# EWElectrode.net
KiCad netlist of a schematic drawn in EAGLE
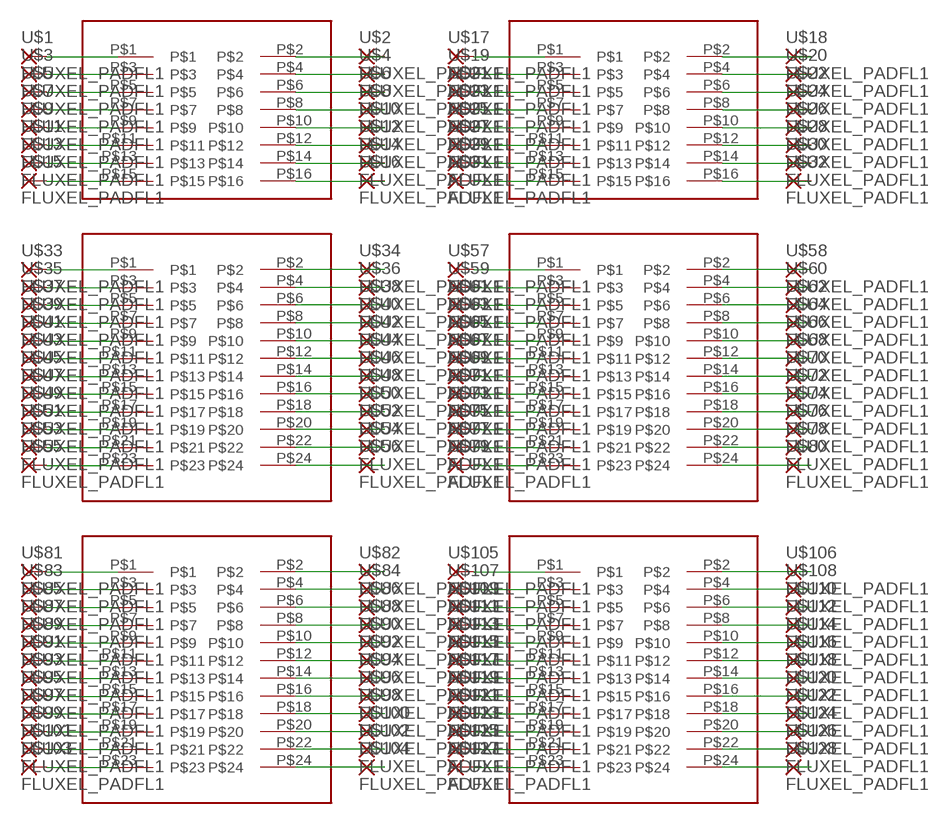
[diagram p0: schematic, sheet 1]

(export (version "E")
  (design (tool "Eeschema 10.0.6"))
  (components
    (comp (ref "J1")
      (value "M20-876P_8X2")
      (footprint "eagle-import:M20-876P_8X2")
      (libsource (lib "eagle-import") (part "M20-876P_8X2"))
    )
    (comp (ref "J2")
      (value "M20-876P_8X2")
      (footprint "eagle-import:M20-876P_8X2")
      (libsource (lib "eagle-import") (part "M20-876P_8X2"))
    )
    (comp (ref "J3")
      (value "M20-876P_12X2")
      (footprint "eagle-import:M20-876P_12X2")
      (libsource (lib "eagle-import") (part "M20-876P_12X2"))
    )
    (comp (ref "J4")
      (value "M20-876P_12X2")
      (footprint "eagle-import:M20-876P_12X2")
      (libsource (lib "eagle-import") (part "M20-876P_12X2"))
    )
    (comp (ref "J5")
      (value "M20-876P_12X2")
      (footprint "eagle-import:M20-876P_12X2")
      (libsource (lib "eagle-import") (part "M20-876P_12X2"))
    )
    (comp (ref "J6")
      (value "M20-876P_12X2")
      (footprint "eagle-import:M20-876P_12X2")
      (libsource (lib "eagle-import") (part "M20-876P_12X2"))
    )
    (comp (ref "U$1")
      (value "FLUXEL_PADFL1")
      (footprint "eagle-import:FLUXEL_PAD")
      (libsource (lib "eagle-import") (part "FLUXEL_PADFL1"))
    )
    (comp (ref "U$2")
      (value "FLUXEL_PADFL1")
      (footprint "eagle-import:FLUXEL_PAD")
      (libsource (lib "eagle-import") (part "FLUXEL_PADFL1"))
    )
    (comp (ref "U$3")
      (value "FLUXEL_PADFL1")
      (footprint "eagle-import:FLUXEL_PAD")
      (libsource (lib "eagle-import") (part "FLUXEL_PADFL1"))
    )
    (comp (ref "U$4")
      (value "FLUXEL_PADFL1")
      (footprint "eagle-import:FLUXEL_PAD")
      (libsource (lib "eagle-import") (part "FLUXEL_PADFL1"))
    )
    (comp (ref "U$5")
      (value "FLUXEL_PADFL1")
      (footprint "eagle-import:FLUXEL_PAD")
      (libsource (lib "eagle-import") (part "FLUXEL_PADFL1"))
    )
    (comp (ref "U$6")
      (value "FLUXEL_PADFL1")
      (footprint "eagle-import:FLUXEL_PAD")
      (libsource (lib "eagle-import") (part "FLUXEL_PADFL1"))
    )
    (comp (ref "U$7")
      (value "FLUXEL_PADFL1")
      (footprint "eagle-import:FLUXEL_PAD")
      (libsource (lib "eagle-import") (part "FLUXEL_PADFL1"))
    )
    (comp (ref "U$8")
      (value "FLUXEL_PADFL1")
      (footprint "eagle-import:FLUXEL_PAD")
      (libsource (lib "eagle-import") (part "FLUXEL_PADFL1"))
    )
    (comp (ref "U$9")
      (value "FLUXEL_PADFL1")
      (footprint "eagle-import:FLUXEL_PAD")
      (libsource (lib "eagle-import") (part "FLUXEL_PADFL1"))
    )
    (comp (ref "U$10")
      (value "FLUXEL_PADFL1")
      (footprint "eagle-import:FLUXEL_PAD")
      (libsource (lib "eagle-import") (part "FLUXEL_PADFL1"))
    )
    (comp (ref "U$11")
      (value "FLUXEL_PADFL1")
      (footprint "eagle-import:FLUXEL_PAD")
      (libsource (lib "eagle-import") (part "FLUXEL_PADFL1"))
    )
    (comp (ref "U$12")
      (value "FLUXEL_PADFL1")
      (footprint "eagle-import:FLUXEL_PAD")
      (libsource (lib "eagle-import") (part "FLUXEL_PADFL1"))
    )
    (comp (ref "U$13")
      (value "FLUXEL_PADFL1")
      (footprint "eagle-import:FLUXEL_PAD")
      (libsource (lib "eagle-import") (part "FLUXEL_PADFL1"))
    )
    (comp (ref "U$14")
      (value "FLUXEL_PADFL1")
      (footprint "eagle-import:FLUXEL_PAD")
      (libsource (lib "eagle-import") (part "FLUXEL_PADFL1"))
    )
    (comp (ref "U$15")
      (value "FLUXEL_PADFL1")
      (footprint "eagle-import:FLUXEL_PAD")
      (libsource (lib "eagle-import") (part "FLUXEL_PADFL1"))
    )
    (comp (ref "U$16")
      (value "FLUXEL_PADFL1")
      (footprint "eagle-import:FLUXEL_PAD")
      (libsource (lib "eagle-import") (part "FLUXEL_PADFL1"))
    )
    (comp (ref "U$17")
      (value "FLUXEL_PADFL1")
      (footprint "eagle-import:FLUXEL_PAD")
      (libsource (lib "eagle-import") (part "FLUXEL_PADFL1"))
    )
    (comp (ref "U$18")
      (value "FLUXEL_PADFL1")
      (footprint "eagle-import:FLUXEL_PAD")
      (libsource (lib "eagle-import") (part "FLUXEL_PADFL1"))
    )
    (comp (ref "U$19")
      (value "FLUXEL_PADFL1")
      (footprint "eagle-import:FLUXEL_PAD")
      (libsource (lib "eagle-import") (part "FLUXEL_PADFL1"))
    )
    (comp (ref "U$20")
      (value "FLUXEL_PADFL1")
      (footprint "eagle-import:FLUXEL_PAD")
      (libsource (lib "eagle-import") (part "FLUXEL_PADFL1"))
    )
    (comp (ref "U$21")
      (value "FLUXEL_PADFL1")
      (footprint "eagle-import:FLUXEL_PAD")
      (libsource (lib "eagle-import") (part "FLUXEL_PADFL1"))
    )
    (comp (ref "U$22")
      (value "FLUXEL_PADFL1")
      (footprint "eagle-import:FLUXEL_PAD")
      (libsource (lib "eagle-import") (part "FLUXEL_PADFL1"))
    )
    (comp (ref "U$23")
      (value "FLUXEL_PADFL1")
      (footprint "eagle-import:FLUXEL_PAD")
      (libsource (lib "eagle-import") (part "FLUXEL_PADFL1"))
    )
    (comp (ref "U$24")
      (value "FLUXEL_PADFL1")
      (footprint "eagle-import:FLUXEL_PAD")
      (libsource (lib "eagle-import") (part "FLUXEL_PADFL1"))
    )
    (comp (ref "U$25")
      (value "FLUXEL_PADFL1")
      (footprint "eagle-import:FLUXEL_PAD")
      (libsource (lib "eagle-import") (part "FLUXEL_PADFL1"))
    )
    (comp (ref "U$26")
      (value "FLUXEL_PADFL1")
      (footprint "eagle-import:FLUXEL_PAD")
      (libsource (lib "eagle-import") (part "FLUXEL_PADFL1"))
    )
    (comp (ref "U$27")
      (value "FLUXEL_PADFL1")
      (footprint "eagle-import:FLUXEL_PAD")
      (libsource (lib "eagle-import") (part "FLUXEL_PADFL1"))
    )
    (comp (ref "U$28")
      (value "FLUXEL_PADFL1")
      (footprint "eagle-import:FLUXEL_PAD")
      (libsource (lib "eagle-import") (part "FLUXEL_PADFL1"))
    )
    (comp (ref "U$29")
      (value "FLUXEL_PADFL1")
      (footprint "eagle-import:FLUXEL_PAD")
      (libsource (lib "eagle-import") (part "FLUXEL_PADFL1"))
    )
    (comp (ref "U$30")
      (value "FLUXEL_PADFL1")
      (footprint "eagle-import:FLUXEL_PAD")
      (libsource (lib "eagle-import") (part "FLUXEL_PADFL1"))
    )
    (comp (ref "U$31")
      (value "FLUXEL_PADFL1")
      (footprint "eagle-import:FLUXEL_PAD")
      (libsource (lib "eagle-import") (part "FLUXEL_PADFL1"))
    )
    (comp (ref "U$32")
      (value "FLUXEL_PADFL1")
      (footprint "eagle-import:FLUXEL_PAD")
      (libsource (lib "eagle-import") (part "FLUXEL_PADFL1"))
    )
    (comp (ref "U$33")
      (value "FLUXEL_PADFL1")
      (footprint "eagle-import:FLUXEL_PAD")
      (libsource (lib "eagle-import") (part "FLUXEL_PADFL1"))
    )
    (comp (ref "U$34")
      (value "FLUXEL_PADFL1")
      (footprint "eagle-import:FLUXEL_PAD")
      (libsource (lib "eagle-import") (part "FLUXEL_PADFL1"))
    )
    (comp (ref "U$35")
      (value "FLUXEL_PADFL1")
      (footprint "eagle-import:FLUXEL_PAD")
      (libsource (lib "eagle-import") (part "FLUXEL_PADFL1"))
    )
    (comp (ref "U$36")
      (value "FLUXEL_PADFL1")
      (footprint "eagle-import:FLUXEL_PAD")
      (libsource (lib "eagle-import") (part "FLUXEL_PADFL1"))
    )
    (comp (ref "U$37")
      (value "FLUXEL_PADFL1")
      (footprint "eagle-import:FLUXEL_PAD")
      (libsource (lib "eagle-import") (part "FLUXEL_PADFL1"))
    )
    (comp (ref "U$38")
      (value "FLUXEL_PADFL1")
      (footprint "eagle-import:FLUXEL_PAD")
      (libsource (lib "eagle-import") (part "FLUXEL_PADFL1"))
    )
    (comp (ref "U$39")
      (value "FLUXEL_PADFL1")
      (footprint "eagle-import:FLUXEL_PAD")
      (libsource (lib "eagle-import") (part "FLUXEL_PADFL1"))
    )
    (comp (ref "U$40")
      (value "FLUXEL_PADFL1")
      (footprint "eagle-import:FLUXEL_PAD")
      (libsource (lib "eagle-import") (part "FLUXEL_PADFL1"))
    )
    (comp (ref "U$41")
      (value "FLUXEL_PADFL1")
      (footprint "eagle-import:FLUXEL_PAD")
      (libsource (lib "eagle-import") (part "FLUXEL_PADFL1"))
    )
    (comp (ref "U$42")
      (value "FLUXEL_PADFL1")
      (footprint "eagle-import:FLUXEL_PAD")
      (libsource (lib "eagle-import") (part "FLUXEL_PADFL1"))
    )
    (comp (ref "U$43")
      (value "FLUXEL_PADFL1")
      (footprint "eagle-import:FLUXEL_PAD")
      (libsource (lib "eagle-import") (part "FLUXEL_PADFL1"))
    )
    (comp (ref "U$44")
      (value "FLUXEL_PADFL1")
      (footprint "eagle-import:FLUXEL_PAD")
      (libsource (lib "eagle-import") (part "FLUXEL_PADFL1"))
    )
    (comp (ref "U$45")
      (value "FLUXEL_PADFL1")
      (footprint "eagle-import:FLUXEL_PAD")
      (libsource (lib "eagle-import") (part "FLUXEL_PADFL1"))
    )
    (comp (ref "U$46")
      (value "FLUXEL_PADFL1")
      (footprint "eagle-import:FLUXEL_PAD")
      (libsource (lib "eagle-import") (part "FLUXEL_PADFL1"))
    )
    (comp (ref "U$47")
      (value "FLUXEL_PADFL1")
      (footprint "eagle-import:FLUXEL_PAD")
      (libsource (lib "eagle-import") (part "FLUXEL_PADFL1"))
    )
    (comp (ref "U$48")
      (value "FLUXEL_PADFL1")
      (footprint "eagle-import:FLUXEL_PAD")
      (libsource (lib "eagle-import") (part "FLUXEL_PADFL1"))
    )
    (comp (ref "U$49")
      (value "FLUXEL_PADFL1")
      (footprint "eagle-import:FLUXEL_PAD")
      (libsource (lib "eagle-import") (part "FLUXEL_PADFL1"))
    )
    (comp (ref "U$50")
      (value "FLUXEL_PADFL1")
      (footprint "eagle-import:FLUXEL_PAD")
      (libsource (lib "eagle-import") (part "FLUXEL_PADFL1"))
    )
    (comp (ref "U$51")
      (value "FLUXEL_PADFL1")
      (footprint "eagle-import:FLUXEL_PAD")
      (libsource (lib "eagle-import") (part "FLUXEL_PADFL1"))
    )
    (comp (ref "U$52")
      (value "FLUXEL_PADFL1")
      (footprint "eagle-import:FLUXEL_PAD")
      (libsource (lib "eagle-import") (part "FLUXEL_PADFL1"))
    )
    (comp (ref "U$53")
      (value "FLUXEL_PADFL1")
      (footprint "eagle-import:FLUXEL_PAD")
      (libsource (lib "eagle-import") (part "FLUXEL_PADFL1"))
    )
    (comp (ref "U$54")
      (value "FLUXEL_PADFL1")
      (footprint "eagle-import:FLUXEL_PAD")
      (libsource (lib "eagle-import") (part "FLUXEL_PADFL1"))
    )
    (comp (ref "U$55")
      (value "FLUXEL_PADFL1")
      (footprint "eagle-import:FLUXEL_PAD")
      (libsource (lib "eagle-import") (part "FLUXEL_PADFL1"))
    )
    (comp (ref "U$56")
      (value "FLUXEL_PADFL1")
      (footprint "eagle-import:FLUXEL_PAD")
      (libsource (lib "eagle-import") (part "FLUXEL_PADFL1"))
    )
    (comp (ref "U$57")
      (value "FLUXEL_PADFL1")
      (footprint "eagle-import:FLUXEL_PAD")
      (libsource (lib "eagle-import") (part "FLUXEL_PADFL1"))
    )
    (comp (ref "U$58")
      (value "FLUXEL_PADFL1")
      (footprint "eagle-import:FLUXEL_PAD")
      (libsource (lib "eagle-import") (part "FLUXEL_PADFL1"))
    )
    (comp (ref "U$59")
      (value "FLUXEL_PADFL1")
      (footprint "eagle-import:FLUXEL_PAD")
      (libsource (lib "eagle-import") (part "FLUXEL_PADFL1"))
    )
    (comp (ref "U$60")
      (value "FLUXEL_PADFL1")
      (footprint "eagle-import:FLUXEL_PAD")
      (libsource (lib "eagle-import") (part "FLUXEL_PADFL1"))
    )
    (comp (ref "U$61")
      (value "FLUXEL_PADFL1")
      (footprint "eagle-import:FLUXEL_PAD")
      (libsource (lib "eagle-import") (part "FLUXEL_PADFL1"))
    )
    (comp (ref "U$62")
      (value "FLUXEL_PADFL1")
      (footprint "eagle-import:FLUXEL_PAD")
      (libsource (lib "eagle-import") (part "FLUXEL_PADFL1"))
    )
    (comp (ref "U$63")
      (value "FLUXEL_PADFL1")
      (footprint "eagle-import:FLUXEL_PAD")
      (libsource (lib "eagle-import") (part "FLUXEL_PADFL1"))
    )
    (comp (ref "U$64")
      (value "FLUXEL_PADFL1")
      (footprint "eagle-import:FLUXEL_PAD")
      (libsource (lib "eagle-import") (part "FLUXEL_PADFL1"))
    )
    (comp (ref "U$65")
      (value "FLUXEL_PADFL1")
      (footprint "eagle-import:FLUXEL_PAD")
      (libsource (lib "eagle-import") (part "FLUXEL_PADFL1"))
    )
    (comp (ref "U$66")
      (value "FLUXEL_PADFL1")
      (footprint "eagle-import:FLUXEL_PAD")
      (libsource (lib "eagle-import") (part "FLUXEL_PADFL1"))
    )
    (comp (ref "U$67")
      (value "FLUXEL_PADFL1")
      (footprint "eagle-import:FLUXEL_PAD")
      (libsource (lib "eagle-import") (part "FLUXEL_PADFL1"))
    )
    (comp (ref "U$68")
      (value "FLUXEL_PADFL1")
      (footprint "eagle-import:FLUXEL_PAD")
      (libsource (lib "eagle-import") (part "FLUXEL_PADFL1"))
    )
    (comp (ref "U$69")
      (value "FLUXEL_PADFL1")
      (footprint "eagle-import:FLUXEL_PAD")
      (libsource (lib "eagle-import") (part "FLUXEL_PADFL1"))
    )
    (comp (ref "U$70")
      (value "FLUXEL_PADFL1")
      (footprint "eagle-import:FLUXEL_PAD")
      (libsource (lib "eagle-import") (part "FLUXEL_PADFL1"))
    )
    (comp (ref "U$71")
      (value "FLUXEL_PADFL1")
      (footprint "eagle-import:FLUXEL_PAD")
      (libsource (lib "eagle-import") (part "FLUXEL_PADFL1"))
    )
    (comp (ref "U$72")
      (value "FLUXEL_PADFL1")
      (footprint "eagle-import:FLUXEL_PAD")
      (libsource (lib "eagle-import") (part "FLUXEL_PADFL1"))
    )
    (comp (ref "U$73")
      (value "FLUXEL_PADFL1")
      (footprint "eagle-import:FLUXEL_PAD")
      (libsource (lib "eagle-import") (part "FLUXEL_PADFL1"))
    )
    (comp (ref "U$74")
      (value "FLUXEL_PADFL1")
      (footprint "eagle-import:FLUXEL_PAD")
      (libsource (lib "eagle-import") (part "FLUXEL_PADFL1"))
    )
    (comp (ref "U$75")
      (value "FLUXEL_PADFL1")
      (footprint "eagle-import:FLUXEL_PAD")
      (libsource (lib "eagle-import") (part "FLUXEL_PADFL1"))
    )
    (comp (ref "U$76")
      (value "FLUXEL_PADFL1")
      (footprint "eagle-import:FLUXEL_PAD")
      (libsource (lib "eagle-import") (part "FLUXEL_PADFL1"))
    )
    (comp (ref "U$77")
      (value "FLUXEL_PADFL1")
      (footprint "eagle-import:FLUXEL_PAD")
      (libsource (lib "eagle-import") (part "FLUXEL_PADFL1"))
    )
    (comp (ref "U$78")
      (value "FLUXEL_PADFL1")
      (footprint "eagle-import:FLUXEL_PAD")
      (libsource (lib "eagle-import") (part "FLUXEL_PADFL1"))
    )
    (comp (ref "U$79")
      (value "FLUXEL_PADFL1")
      (footprint "eagle-import:FLUXEL_PAD")
      (libsource (lib "eagle-import") (part "FLUXEL_PADFL1"))
    )
    (comp (ref "U$80")
      (value "FLUXEL_PADFL1")
      (footprint "eagle-import:FLUXEL_PAD")
      (libsource (lib "eagle-import") (part "FLUXEL_PADFL1"))
    )
    (comp (ref "U$81")
      (value "FLUXEL_PADFL1")
      (footprint "eagle-import:FLUXEL_PAD")
      (libsource (lib "eagle-import") (part "FLUXEL_PADFL1"))
    )
    (comp (ref "U$82")
      (value "FLUXEL_PADFL1")
      (footprint "eagle-import:FLUXEL_PAD")
      (libsource (lib "eagle-import") (part "FLUXEL_PADFL1"))
    )
    (comp (ref "U$83")
      (value "FLUXEL_PADFL1")
      (footprint "eagle-import:FLUXEL_PAD")
      (libsource (lib "eagle-import") (part "FLUXEL_PADFL1"))
    )
    (comp (ref "U$84")
      (value "FLUXEL_PADFL1")
      (footprint "eagle-import:FLUXEL_PAD")
      (libsource (lib "eagle-import") (part "FLUXEL_PADFL1"))
    )
    (comp (ref "U$85")
      (value "FLUXEL_PADFL1")
      (footprint "eagle-import:FLUXEL_PAD")
      (libsource (lib "eagle-import") (part "FLUXEL_PADFL1"))
    )
    (comp (ref "U$86")
      (value "FLUXEL_PADFL1")
      (footprint "eagle-import:FLUXEL_PAD")
      (libsource (lib "eagle-import") (part "FLUXEL_PADFL1"))
    )
    (comp (ref "U$87")
      (value "FLUXEL_PADFL1")
      (footprint "eagle-import:FLUXEL_PAD")
      (libsource (lib "eagle-import") (part "FLUXEL_PADFL1"))
    )
    (comp (ref "U$88")
      (value "FLUXEL_PADFL1")
      (footprint "eagle-import:FLUXEL_PAD")
      (libsource (lib "eagle-import") (part "FLUXEL_PADFL1"))
    )
    (comp (ref "U$89")
      (value "FLUXEL_PADFL1")
      (footprint "eagle-import:FLUXEL_PAD")
      (libsource (lib "eagle-import") (part "FLUXEL_PADFL1"))
    )
    (comp (ref "U$90")
      (value "FLUXEL_PADFL1")
      (footprint "eagle-import:FLUXEL_PAD")
      (libsource (lib "eagle-import") (part "FLUXEL_PADFL1"))
    )
    (comp (ref "U$91")
      (value "FLUXEL_PADFL1")
      (footprint "eagle-import:FLUXEL_PAD")
      (libsource (lib "eagle-import") (part "FLUXEL_PADFL1"))
    )
    (comp (ref "U$92")
      (value "FLUXEL_PADFL1")
      (footprint "eagle-import:FLUXEL_PAD")
      (libsource (lib "eagle-import") (part "FLUXEL_PADFL1"))
    )
    (comp (ref "U$93")
      (value "FLUXEL_PADFL1")
      (footprint "eagle-import:FLUXEL_PAD")
      (libsource (lib "eagle-import") (part "FLUXEL_PADFL1"))
    )
    (comp (ref "U$94")
      (value "FLUXEL_PADFL1")
      (footprint "eagle-import:FLUXEL_PAD")
      (libsource (lib "eagle-import") (part "FLUXEL_PADFL1"))
    )
    (comp (ref "U$95")
      (value "FLUXEL_PADFL1")
      (footprint "eagle-import:FLUXEL_PAD")
      (libsource (lib "eagle-import") (part "FLUXEL_PADFL1"))
    )
    (comp (ref "U$96")
      (value "FLUXEL_PADFL1")
      (footprint "eagle-import:FLUXEL_PAD")
      (libsource (lib "eagle-import") (part "FLUXEL_PADFL1"))
    )
    (comp (ref "U$97")
      (value "FLUXEL_PADFL1")
      (footprint "eagle-import:FLUXEL_PAD")
      (libsource (lib "eagle-import") (part "FLUXEL_PADFL1"))
    )
    (comp (ref "U$98")
      (value "FLUXEL_PADFL1")
      (footprint "eagle-import:FLUXEL_PAD")
      (libsource (lib "eagle-import") (part "FLUXEL_PADFL1"))
    )
    (comp (ref "U$99")
      (value "FLUXEL_PADFL1")
      (footprint "eagle-import:FLUXEL_PAD")
      (libsource (lib "eagle-import") (part "FLUXEL_PADFL1"))
    )
    (comp (ref "U$100")
      (value "FLUXEL_PADFL1")
      (footprint "eagle-import:FLUXEL_PAD")
      (libsource (lib "eagle-import") (part "FLUXEL_PADFL1"))
    )
    (comp (ref "U$101")
      (value "FLUXEL_PADFL1")
      (footprint "eagle-import:FLUXEL_PAD")
      (libsource (lib "eagle-import") (part "FLUXEL_PADFL1"))
    )
    (comp (ref "U$102")
      (value "FLUXEL_PADFL1")
      (footprint "eagle-import:FLUXEL_PAD")
      (libsource (lib "eagle-import") (part "FLUXEL_PADFL1"))
    )
    (comp (ref "U$103")
      (value "FLUXEL_PADFL1")
      (footprint "eagle-import:FLUXEL_PAD")
      (libsource (lib "eagle-import") (part "FLUXEL_PADFL1"))
    )
    (comp (ref "U$104")
      (value "FLUXEL_PADFL1")
      (footprint "eagle-import:FLUXEL_PAD")
      (libsource (lib "eagle-import") (part "FLUXEL_PADFL1"))
    )
    (comp (ref "U$105")
      (value "FLUXEL_PADFL1")
      (footprint "eagle-import:FLUXEL_PAD")
      (libsource (lib "eagle-import") (part "FLUXEL_PADFL1"))
    )
    (comp (ref "U$106")
      (value "FLUXEL_PADFL1")
      (footprint "eagle-import:FLUXEL_PAD")
      (libsource (lib "eagle-import") (part "FLUXEL_PADFL1"))
    )
    (comp (ref "U$107")
      (value "FLUXEL_PADFL1")
      (footprint "eagle-import:FLUXEL_PAD")
      (libsource (lib "eagle-import") (part "FLUXEL_PADFL1"))
    )
    (comp (ref "U$108")
      (value "FLUXEL_PADFL1")
      (footprint "eagle-import:FLUXEL_PAD")
      (libsource (lib "eagle-import") (part "FLUXEL_PADFL1"))
    )
    (comp (ref "U$109")
      (value "FLUXEL_PADFL1")
      (footprint "eagle-import:FLUXEL_PAD")
      (libsource (lib "eagle-import") (part "FLUXEL_PADFL1"))
    )
    (comp (ref "U$110")
      (value "FLUXEL_PADFL1")
      (footprint "eagle-import:FLUXEL_PAD")
      (libsource (lib "eagle-import") (part "FLUXEL_PADFL1"))
    )
    (comp (ref "U$111")
      (value "FLUXEL_PADFL1")
      (footprint "eagle-import:FLUXEL_PAD")
      (libsource (lib "eagle-import") (part "FLUXEL_PADFL1"))
    )
    (comp (ref "U$112")
      (value "FLUXEL_PADFL1")
      (footprint "eagle-import:FLUXEL_PAD")
      (libsource (lib "eagle-import") (part "FLUXEL_PADFL1"))
    )
    (comp (ref "U$113")
      (value "FLUXEL_PADFL1")
      (footprint "eagle-import:FLUXEL_PAD")
      (libsource (lib "eagle-import") (part "FLUXEL_PADFL1"))
    )
    (comp (ref "U$114")
      (value "FLUXEL_PADFL1")
      (footprint "eagle-import:FLUXEL_PAD")
      (libsource (lib "eagle-import") (part "FLUXEL_PADFL1"))
    )
    (comp (ref "U$115")
      (value "FLUXEL_PADFL1")
      (footprint "eagle-import:FLUXEL_PAD")
      (libsource (lib "eagle-import") (part "FLUXEL_PADFL1"))
    )
    (comp (ref "U$116")
      (value "FLUXEL_PADFL1")
      (footprint "eagle-import:FLUXEL_PAD")
      (libsource (lib "eagle-import") (part "FLUXEL_PADFL1"))
    )
    (comp (ref "U$117")
      (value "FLUXEL_PADFL1")
      (footprint "eagle-import:FLUXEL_PAD")
      (libsource (lib "eagle-import") (part "FLUXEL_PADFL1"))
    )
    (comp (ref "U$118")
      (value "FLUXEL_PADFL1")
      (footprint "eagle-import:FLUXEL_PAD")
      (libsource (lib "eagle-import") (part "FLUXEL_PADFL1"))
    )
    (comp (ref "U$119")
      (value "FLUXEL_PADFL1")
      (footprint "eagle-import:FLUXEL_PAD")
      (libsource (lib "eagle-import") (part "FLUXEL_PADFL1"))
    )
    (comp (ref "U$120")
      (value "FLUXEL_PADFL1")
      (footprint "eagle-import:FLUXEL_PAD")
      (libsource (lib "eagle-import") (part "FLUXEL_PADFL1"))
    )
    (comp (ref "U$121")
      (value "FLUXEL_PADFL1")
      (footprint "eagle-import:FLUXEL_PAD")
      (libsource (lib "eagle-import") (part "FLUXEL_PADFL1"))
    )
    (comp (ref "U$122")
      (value "FLUXEL_PADFL1")
      (footprint "eagle-import:FLUXEL_PAD")
      (libsource (lib "eagle-import") (part "FLUXEL_PADFL1"))
    )
    (comp (ref "U$123")
      (value "FLUXEL_PADFL1")
      (footprint "eagle-import:FLUXEL_PAD")
      (libsource (lib "eagle-import") (part "FLUXEL_PADFL1"))
    )
    (comp (ref "U$124")
      (value "FLUXEL_PADFL1")
      (footprint "eagle-import:FLUXEL_PAD")
      (libsource (lib "eagle-import") (part "FLUXEL_PADFL1"))
    )
    (comp (ref "U$125")
      (value "FLUXEL_PADFL1")
      (footprint "eagle-import:FLUXEL_PAD")
      (libsource (lib "eagle-import") (part "FLUXEL_PADFL1"))
    )
    (comp (ref "U$126")
      (value "FLUXEL_PADFL1")
      (footprint "eagle-import:FLUXEL_PAD")
      (libsource (lib "eagle-import") (part "FLUXEL_PADFL1"))
    )
    (comp (ref "U$127")
      (value "FLUXEL_PADFL1")
      (footprint "eagle-import:FLUXEL_PAD")
      (libsource (lib "eagle-import") (part "FLUXEL_PADFL1"))
    )
    (comp (ref "U$128")
      (value "FLUXEL_PADFL1")
      (footprint "eagle-import:FLUXEL_PAD")
      (libsource (lib "eagle-import") (part "FLUXEL_PADFL1"))
    )
  )
  (nets
    (net (code "1") (name "Net-(U$1-P)") (class "Default")
      (node (ref "J1") (pin "P$1") (pinfunction "P$1_P$1") (pintype "bidirectional"))
      (node (ref "U$1") (pin "1") (pinfunction "P_1") (pintype "passive"))
    )
    (net (code "2") (name "Net-(U$2-P)") (class "Default")
      (node (ref "J1") (pin "P$2") (pinfunction "P$2_P$2") (pintype "bidirectional"))
      (node (ref "U$2") (pin "1") (pinfunction "P_1") (pintype "passive"))
    )
    (net (code "3") (name "Net-(U$3-P)") (class "Default")
      (node (ref "J1") (pin "P$3") (pinfunction "P$3_P$3") (pintype "bidirectional"))
      (node (ref "U$3") (pin "1") (pinfunction "P_1") (pintype "passive"))
    )
    (net (code "4") (name "Net-(U$4-P)") (class "Default")
      (node (ref "J1") (pin "P$4") (pinfunction "P$4_P$4") (pintype "bidirectional"))
      (node (ref "U$4") (pin "1") (pinfunction "P_1") (pintype "passive"))
    )
    (net (code "5") (name "Net-(U$5-P)") (class "Default")
      (node (ref "J1") (pin "P$5") (pinfunction "P$5_P$5") (pintype "bidirectional"))
      (node (ref "U$5") (pin "1") (pinfunction "P_1") (pintype "passive"))
    )
    (net (code "6") (name "Net-(U$6-P)") (class "Default")
      (node (ref "J1") (pin "P$6") (pinfunction "P$6_P$6") (pintype "bidirectional"))
      (node (ref "U$6") (pin "1") (pinfunction "P_1") (pintype "passive"))
    )
    (net (code "7") (name "Net-(U$7-P)") (class "Default")
      (node (ref "J1") (pin "P$7") (pinfunction "P$7_P$7") (pintype "bidirectional"))
      (node (ref "U$7") (pin "1") (pinfunction "P_1") (pintype "passive"))
    )
    (net (code "8") (name "Net-(U$8-P)") (class "Default")
      (node (ref "J1") (pin "P$8") (pinfunction "P$8_P$8") (pintype "bidirectional"))
      (node (ref "U$8") (pin "1") (pinfunction "P_1") (pintype "passive"))
    )
    (net (code "9") (name "Net-(U$9-P)") (class "Default")
      (node (ref "J1") (pin "P$9") (pinfunction "P$9_P$9") (pintype "bidirectional"))
      (node (ref "U$9") (pin "1") (pinfunction "P_1") (pintype "passive"))
    )
    (net (code "10") (name "Net-(U$10-P)") (class "Default")
      (node (ref "J1") (pin "P$10") (pinfunction "P$10_P$10") (pintype "bidirectional"))
      (node (ref "U$10") (pin "1") (pinfunction "P_1") (pintype "passive"))
    )
    (net (code "11") (name "Net-(U$11-P)") (class "Default")
      (node (ref "J1") (pin "P$11") (pinfunction "P$11_P$11") (pintype "bidirectional"))
      (node (ref "U$11") (pin "1") (pinfunction "P_1") (pintype "passive"))
    )
    (net (code "12") (name "Net-(U$12-P)") (class "Default")
      (node (ref "J1") (pin "P$12") (pinfunction "P$12_P$12") (pintype "bidirectional"))
      (node (ref "U$12") (pin "1") (pinfunction "P_1") (pintype "passive"))
    )
    (net (code "13") (name "Net-(U$13-P)") (class "Default")
      (node (ref "J1") (pin "P$13") (pinfunction "P$13_P$13") (pintype "bidirectional"))
      (node (ref "U$13") (pin "1") (pinfunction "P_1") (pintype "passive"))
    )
    (net (code "14") (name "Net-(U$14-P)") (class "Default")
      (node (ref "J1") (pin "P$14") (pinfunction "P$14_P$14") (pintype "bidirectional"))
      (node (ref "U$14") (pin "1") (pinfunction "P_1") (pintype "passive"))
    )
    (net (code "15") (name "Net-(U$15-P)") (class "Default")
      (node (ref "J1") (pin "P$15") (pinfunction "P$15_P$15") (pintype "bidirectional"))
      (node (ref "U$15") (pin "1") (pinfunction "P_1") (pintype "passive"))
    )
    (net (code "16") (name "Net-(U$16-P)") (class "Default")
      (node (ref "J1") (pin "P$16") (pinfunction "P$16_P$16") (pintype "bidirectional"))
      (node (ref "U$16") (pin "1") (pinfunction "P_1") (pintype "passive"))
    )
    (net (code "17") (name "Net-(U$17-P)") (class "Default")
      (node (ref "J2") (pin "P$1") (pinfunction "P$1_P$1") (pintype "bidirectional"))
      (node (ref "U$17") (pin "1") (pinfunction "P_1") (pintype "passive"))
    )
    (net (code "18") (name "Net-(U$18-P)") (class "Default")
      (node (ref "J2") (pin "P$2") (pinfunction "P$2_P$2") (pintype "bidirectional"))
      (node (ref "U$18") (pin "1") (pinfunction "P_1") (pintype "passive"))
    )
    (net (code "19") (name "Net-(U$19-P)") (class "Default")
      (node (ref "J2") (pin "P$3") (pinfunction "P$3_P$3") (pintype "bidirectional"))
      (node (ref "U$19") (pin "1") (pinfunction "P_1") (pintype "passive"))
    )
    (net (code "20") (name "Net-(U$20-P)") (class "Default")
      (node (ref "J2") (pin "P$4") (pinfunction "P$4_P$4") (pintype "bidirectional"))
      (node (ref "U$20") (pin "1") (pinfunction "P_1") (pintype "passive"))
    )
    (net (code "21") (name "Net-(U$21-P)") (class "Default")
      (node (ref "J2") (pin "P$5") (pinfunction "P$5_P$5") (pintype "bidirectional"))
      (node (ref "U$21") (pin "1") (pinfunction "P_1") (pintype "passive"))
    )
    (net (code "22") (name "Net-(U$22-P)") (class "Default")
      (node (ref "J2") (pin "P$6") (pinfunction "P$6_P$6") (pintype "bidirectional"))
      (node (ref "U$22") (pin "1") (pinfunction "P_1") (pintype "passive"))
    )
    (net (code "23") (name "Net-(U$23-P)") (class "Default")
      (node (ref "J2") (pin "P$7") (pinfunction "P$7_P$7") (pintype "bidirectional"))
      (node (ref "U$23") (pin "1") (pinfunction "P_1") (pintype "passive"))
    )
    (net (code "24") (name "Net-(U$24-P)") (class "Default")
      (node (ref "J2") (pin "P$8") (pinfunction "P$8_P$8") (pintype "bidirectional"))
      (node (ref "U$24") (pin "1") (pinfunction "P_1") (pintype "passive"))
    )
    (net (code "25") (name "Net-(U$25-P)") (class "Default")
      (node (ref "J2") (pin "P$9") (pinfunction "P$9_P$9") (pintype "bidirectional"))
      (node (ref "U$25") (pin "1") (pinfunction "P_1") (pintype "passive"))
    )
    (net (code "26") (name "Net-(U$26-P)") (class "Default")
      (node (ref "J2") (pin "P$10") (pinfunction "P$10_P$10") (pintype "bidirectional"))
      (node (ref "U$26") (pin "1") (pinfunction "P_1") (pintype "passive"))
    )
    (net (code "27") (name "Net-(U$27-P)") (class "Default")
      (node (ref "J2") (pin "P$11") (pinfunction "P$11_P$11") (pintype "bidirectional"))
      (node (ref "U$27") (pin "1") (pinfunction "P_1") (pintype "passive"))
    )
    (net (code "28") (name "Net-(U$28-P)") (class "Default")
      (node (ref "J2") (pin "P$12") (pinfunction "P$12_P$12") (pintype "bidirectional"))
      (node (ref "U$28") (pin "1") (pinfunction "P_1") (pintype "passive"))
    )
    (net (code "29") (name "Net-(U$29-P)") (class "Default")
      (node (ref "J2") (pin "P$13") (pinfunction "P$13_P$13") (pintype "bidirectional"))
      (node (ref "U$29") (pin "1") (pinfunction "P_1") (pintype "passive"))
    )
    (net (code "30") (name "Net-(U$30-P)") (class "Default")
      (node (ref "J2") (pin "P$14") (pinfunction "P$14_P$14") (pintype "bidirectional"))
      (node (ref "U$30") (pin "1") (pinfunction "P_1") (pintype "passive"))
    )
    (net (code "31") (name "Net-(U$31-P)") (class "Default")
      (node (ref "J2") (pin "P$15") (pinfunction "P$15_P$15") (pintype "bidirectional"))
      (node (ref "U$31") (pin "1") (pinfunction "P_1") (pintype "passive"))
    )
    (net (code "32") (name "Net-(U$32-P)") (class "Default")
      (node (ref "J2") (pin "P$16") (pinfunction "P$16_P$16") (pintype "bidirectional"))
      (node (ref "U$32") (pin "1") (pinfunction "P_1") (pintype "passive"))
    )
    (net (code "33") (name "Net-(U$33-P)") (class "Default")
      (node (ref "J3") (pin "P$1") (pinfunction "P$1_P$1") (pintype "bidirectional"))
      (node (ref "U$33") (pin "1") (pinfunction "P_1") (pintype "passive"))
    )
    (net (code "34") (name "Net-(U$34-P)") (class "Default")
      (node (ref "J3") (pin "P$2") (pinfunction "P$2_P$2") (pintype "bidirectional"))
      (node (ref "U$34") (pin "1") (pinfunction "P_1") (pintype "passive"))
    )
    (net (code "35") (name "Net-(U$35-P)") (class "Default")
      (node (ref "J3") (pin "P$3") (pinfunction "P$3_P$3") (pintype "bidirectional"))
      (node (ref "U$35") (pin "1") (pinfunction "P_1") (pintype "passive"))
    )
    (net (code "36") (name "Net-(U$36-P)") (class "Default")
      (node (ref "J3") (pin "P$4") (pinfunction "P$4_P$4") (pintype "bidirectional"))
      (node (ref "U$36") (pin "1") (pinfunction "P_1") (pintype "passive"))
    )
    (net (code "37") (name "Net-(U$37-P)") (class "Default")
      (node (ref "J3") (pin "P$5") (pinfunction "P$5_P$5") (pintype "bidirectional"))
      (node (ref "U$37") (pin "1") (pinfunction "P_1") (pintype "passive"))
    )
    (net (code "38") (name "Net-(U$38-P)") (class "Default")
      (node (ref "J3") (pin "P$6") (pinfunction "P$6_P$6") (pintype "bidirectional"))
      (node (ref "U$38") (pin "1") (pinfunction "P_1") (pintype "passive"))
    )
    (net (code "39") (name "Net-(U$39-P)") (class "Default")
      (node (ref "J3") (pin "P$7") (pinfunction "P$7_P$7") (pintype "bidirectional"))
      (node (ref "U$39") (pin "1") (pinfunction "P_1") (pintype "passive"))
    )
    (net (code "40") (name "Net-(U$40-P)") (class "Default")
      (node (ref "J3") (pin "P$8") (pinfunction "P$8_P$8") (pintype "bidirectional"))
      (node (ref "U$40") (pin "1") (pinfunction "P_1") (pintype "passive"))
    )
    (net (code "41") (name "Net-(U$41-P)") (class "Default")
      (node (ref "J3") (pin "P$9") (pinfunction "P$9_P$9") (pintype "bidirectional"))
      (node (ref "U$41") (pin "1") (pinfunction "P_1") (pintype "passive"))
    )
    (net (code "42") (name "Net-(U$42-P)") (class "Default")
      (node (ref "J3") (pin "P$10") (pinfunction "P$10_P$10") (pintype "bidirectional"))
      (node (ref "U$42") (pin "1") (pinfunction "P_1") (pintype "passive"))
    )
    (net (code "43") (name "Net-(U$43-P)") (class "Default")
      (node (ref "J3") (pin "P$11") (pinfunction "P$11_P$11") (pintype "bidirectional"))
      (node (ref "U$43") (pin "1") (pinfunction "P_1") (pintype "passive"))
    )
    (net (code "44") (name "Net-(U$44-P)") (class "Default")
      (node (ref "J3") (pin "P$12") (pinfunction "P$12_P$12") (pintype "bidirectional"))
      (node (ref "U$44") (pin "1") (pinfunction "P_1") (pintype "passive"))
    )
    (net (code "45") (name "Net-(U$45-P)") (class "Default")
      (node (ref "J3") (pin "P$13") (pinfunction "P$13_P$13") (pintype "bidirectional"))
      (node (ref "U$45") (pin "1") (pinfunction "P_1") (pintype "passive"))
    )
    (net (code "46") (name "Net-(U$46-P)") (class "Default")
      (node (ref "J3") (pin "P$14") (pinfunction "P$14_P$14") (pintype "bidirectional"))
      (node (ref "U$46") (pin "1") (pinfunction "P_1") (pintype "passive"))
    )
    (net (code "47") (name "Net-(U$47-P)") (class "Default")
      (node (ref "J3") (pin "P$15") (pinfunction "P$15_P$15") (pintype "bidirectional"))
      (node (ref "U$47") (pin "1") (pinfunction "P_1") (pintype "passive"))
    )
    (net (code "48") (name "Net-(U$48-P)") (class "Default")
      (node (ref "J3") (pin "P$16") (pinfunction "P$16_P$16") (pintype "bidirectional"))
      (node (ref "U$48") (pin "1") (pinfunction "P_1") (pintype "passive"))
    )
    (net (code "49") (name "Net-(U$49-P)") (class "Default")
      (node (ref "J3") (pin "P$17") (pinfunction "P$17_P$17") (pintype "bidirectional"))
      (node (ref "U$49") (pin "1") (pinfunction "P_1") (pintype "passive"))
    )
    (net (code "50") (name "Net-(U$50-P)") (class "Default")
      (node (ref "J3") (pin "P$18") (pinfunction "P$18_P$18") (pintype "bidirectional"))
      (node (ref "U$50") (pin "1") (pinfunction "P_1") (pintype "passive"))
    )
    (net (code "51") (name "Net-(U$51-P)") (class "Default")
      (node (ref "J3") (pin "P$19") (pinfunction "P$19_P$19") (pintype "bidirectional"))
      (node (ref "U$51") (pin "1") (pinfunction "P_1") (pintype "passive"))
    )
    (net (code "52") (name "Net-(U$52-P)") (class "Default")
      (node (ref "J3") (pin "P$20") (pinfunction "P$20_P$20") (pintype "bidirectional"))
      (node (ref "U$52") (pin "1") (pinfunction "P_1") (pintype "passive"))
    )
    (net (code "53") (name "Net-(U$53-P)") (class "Default")
      (node (ref "J3") (pin "P$21") (pinfunction "P$21_P$21") (pintype "bidirectional"))
      (node (ref "U$53") (pin "1") (pinfunction "P_1") (pintype "passive"))
    )
    (net (code "54") (name "Net-(U$54-P)") (class "Default")
      (node (ref "J3") (pin "P$22") (pinfunction "P$22_P$22") (pintype "bidirectional"))
      (node (ref "U$54") (pin "1") (pinfunction "P_1") (pintype "passive"))
    )
    (net (code "55") (name "Net-(U$55-P)") (class "Default")
      (node (ref "J3") (pin "P$23") (pinfunction "P$23_P$23") (pintype "bidirectional"))
      (node (ref "U$55") (pin "1") (pinfunction "P_1") (pintype "passive"))
    )
    (net (code "56") (name "Net-(U$56-P)") (class "Default")
      (node (ref "J3") (pin "P$24") (pinfunction "P$24_P$24") (pintype "bidirectional"))
      (node (ref "U$56") (pin "1") (pinfunction "P_1") (pintype "passive"))
    )
    (net (code "57") (name "Net-(U$57-P)") (class "Default")
      (node (ref "J4") (pin "P$1") (pinfunction "P$1_P$1") (pintype "bidirectional"))
      (node (ref "U$57") (pin "1") (pinfunction "P_1") (pintype "passive"))
    )
    (net (code "58") (name "Net-(U$58-P)") (class "Default")
      (node (ref "J4") (pin "P$2") (pinfunction "P$2_P$2") (pintype "bidirectional"))
      (node (ref "U$58") (pin "1") (pinfunction "P_1") (pintype "passive"))
    )
    (net (code "59") (name "Net-(U$59-P)") (class "Default")
      (node (ref "J4") (pin "P$3") (pinfunction "P$3_P$3") (pintype "bidirectional"))
      (node (ref "U$59") (pin "1") (pinfunction "P_1") (pintype "passive"))
    )
    (net (code "60") (name "Net-(U$60-P)") (class "Default")
      (node (ref "J4") (pin "P$4") (pinfunction "P$4_P$4") (pintype "bidirectional"))
      (node (ref "U$60") (pin "1") (pinfunction "P_1") (pintype "passive"))
    )
    (net (code "61") (name "Net-(U$61-P)") (class "Default")
      (node (ref "J4") (pin "P$5") (pinfunction "P$5_P$5") (pintype "bidirectional"))
      (node (ref "U$61") (pin "1") (pinfunction "P_1") (pintype "passive"))
    )
    (net (code "62") (name "Net-(U$62-P)") (class "Default")
      (node (ref "J4") (pin "P$6") (pinfunction "P$6_P$6") (pintype "bidirectional"))
      (node (ref "U$62") (pin "1") (pinfunction "P_1") (pintype "passive"))
    )
    (net (code "63") (name "Net-(U$63-P)") (class "Default")
      (node (ref "J4") (pin "P$7") (pinfunction "P$7_P$7") (pintype "bidirectional"))
      (node (ref "U$63") (pin "1") (pinfunction "P_1") (pintype "passive"))
    )
    (net (code "64") (name "Net-(U$64-P)") (class "Default")
      (node (ref "J4") (pin "P$8") (pinfunction "P$8_P$8") (pintype "bidirectional"))
      (node (ref "U$64") (pin "1") (pinfunction "P_1") (pintype "passive"))
    )
    (net (code "65") (name "Net-(U$65-P)") (class "Default")
      (node (ref "J4") (pin "P$9") (pinfunction "P$9_P$9") (pintype "bidirectional"))
      (node (ref "U$65") (pin "1") (pinfunction "P_1") (pintype "passive"))
    )
    (net (code "66") (name "Net-(U$66-P)") (class "Default")
      (node (ref "J4") (pin "P$10") (pinfunction "P$10_P$10") (pintype "bidirectional"))
      (node (ref "U$66") (pin "1") (pinfunction "P_1") (pintype "passive"))
    )
    (net (code "67") (name "Net-(U$67-P)") (class "Default")
      (node (ref "J4") (pin "P$11") (pinfunction "P$11_P$11") (pintype "bidirectional"))
      (node (ref "U$67") (pin "1") (pinfunction "P_1") (pintype "passive"))
    )
    (net (code "68") (name "Net-(U$68-P)") (class "Default")
      (node (ref "J4") (pin "P$12") (pinfunction "P$12_P$12") (pintype "bidirectional"))
      (node (ref "U$68") (pin "1") (pinfunction "P_1") (pintype "passive"))
    )
    (net (code "69") (name "Net-(U$69-P)") (class "Default")
      (node (ref "J4") (pin "P$13") (pinfunction "P$13_P$13") (pintype "bidirectional"))
      (node (ref "U$69") (pin "1") (pinfunction "P_1") (pintype "passive"))
    )
    (net (code "70") (name "Net-(U$70-P)") (class "Default")
      (node (ref "J4") (pin "P$14") (pinfunction "P$14_P$14") (pintype "bidirectional"))
      (node (ref "U$70") (pin "1") (pinfunction "P_1") (pintype "passive"))
    )
    (net (code "71") (name "Net-(U$71-P)") (class "Default")
      (node (ref "J4") (pin "P$15") (pinfunction "P$15_P$15") (pintype "bidirectional"))
      (node (ref "U$71") (pin "1") (pinfunction "P_1") (pintype "passive"))
    )
    (net (code "72") (name "Net-(U$72-P)") (class "Default")
      (node (ref "J4") (pin "P$16") (pinfunction "P$16_P$16") (pintype "bidirectional"))
      (node (ref "U$72") (pin "1") (pinfunction "P_1") (pintype "passive"))
    )
    (net (code "73") (name "Net-(U$73-P)") (class "Default")
      (node (ref "J4") (pin "P$17") (pinfunction "P$17_P$17") (pintype "bidirectional"))
      (node (ref "U$73") (pin "1") (pinfunction "P_1") (pintype "passive"))
    )
    (net (code "74") (name "Net-(U$74-P)") (class "Default")
      (node (ref "J4") (pin "P$18") (pinfunction "P$18_P$18") (pintype "bidirectional"))
      (node (ref "U$74") (pin "1") (pinfunction "P_1") (pintype "passive"))
    )
    (net (code "75") (name "Net-(U$75-P)") (class "Default")
      (node (ref "J4") (pin "P$19") (pinfunction "P$19_P$19") (pintype "bidirectional"))
      (node (ref "U$75") (pin "1") (pinfunction "P_1") (pintype "passive"))
    )
    (net (code "76") (name "Net-(U$76-P)") (class "Default")
      (node (ref "J4") (pin "P$20") (pinfunction "P$20_P$20") (pintype "bidirectional"))
      (node (ref "U$76") (pin "1") (pinfunction "P_1") (pintype "passive"))
    )
    (net (code "77") (name "Net-(U$77-P)") (class "Default")
      (node (ref "J4") (pin "P$21") (pinfunction "P$21_P$21") (pintype "bidirectional"))
      (node (ref "U$77") (pin "1") (pinfunction "P_1") (pintype "passive"))
    )
    (net (code "78") (name "Net-(U$78-P)") (class "Default")
      (node (ref "J4") (pin "P$22") (pinfunction "P$22_P$22") (pintype "bidirectional"))
      (node (ref "U$78") (pin "1") (pinfunction "P_1") (pintype "passive"))
    )
    (net (code "79") (name "Net-(U$79-P)") (class "Default")
      (node (ref "J4") (pin "P$23") (pinfunction "P$23_P$23") (pintype "bidirectional"))
      (node (ref "U$79") (pin "1") (pinfunction "P_1") (pintype "passive"))
    )
    (net (code "80") (name "Net-(U$80-P)") (class "Default")
      (node (ref "J4") (pin "P$24") (pinfunction "P$24_P$24") (pintype "bidirectional"))
      (node (ref "U$80") (pin "1") (pinfunction "P_1") (pintype "passive"))
    )
    (net (code "81") (name "Net-(U$81-P)") (class "Default")
      (node (ref "J5") (pin "P$1") (pinfunction "P$1_P$1") (pintype "bidirectional"))
      (node (ref "U$81") (pin "1") (pinfunction "P_1") (pintype "passive"))
    )
    (net (code "82") (name "Net-(U$82-P)") (class "Default")
      (node (ref "J5") (pin "P$2") (pinfunction "P$2_P$2") (pintype "bidirectional"))
      (node (ref "U$82") (pin "1") (pinfunction "P_1") (pintype "passive"))
    )
    (net (code "83") (name "Net-(U$83-P)") (class "Default")
      (node (ref "J5") (pin "P$3") (pinfunction "P$3_P$3") (pintype "bidirectional"))
      (node (ref "U$83") (pin "1") (pinfunction "P_1") (pintype "passive"))
    )
    (net (code "84") (name "Net-(U$84-P)") (class "Default")
      (node (ref "J5") (pin "P$4") (pinfunction "P$4_P$4") (pintype "bidirectional"))
      (node (ref "U$84") (pin "1") (pinfunction "P_1") (pintype "passive"))
    )
    (net (code "85") (name "Net-(U$85-P)") (class "Default")
      (node (ref "J5") (pin "P$5") (pinfunction "P$5_P$5") (pintype "bidirectional"))
      (node (ref "U$85") (pin "1") (pinfunction "P_1") (pintype "passive"))
    )
    (net (code "86") (name "Net-(U$86-P)") (class "Default")
      (node (ref "J5") (pin "P$6") (pinfunction "P$6_P$6") (pintype "bidirectional"))
      (node (ref "U$86") (pin "1") (pinfunction "P_1") (pintype "passive"))
    )
    (net (code "87") (name "Net-(U$87-P)") (class "Default")
      (node (ref "J5") (pin "P$7") (pinfunction "P$7_P$7") (pintype "bidirectional"))
      (node (ref "U$87") (pin "1") (pinfunction "P_1") (pintype "passive"))
    )
    (net (code "88") (name "Net-(U$88-P)") (class "Default")
      (node (ref "J5") (pin "P$8") (pinfunction "P$8_P$8") (pintype "bidirectional"))
      (node (ref "U$88") (pin "1") (pinfunction "P_1") (pintype "passive"))
    )
    (net (code "89") (name "Net-(U$89-P)") (class "Default")
      (node (ref "J5") (pin "P$9") (pinfunction "P$9_P$9") (pintype "bidirectional"))
      (node (ref "U$89") (pin "1") (pinfunction "P_1") (pintype "passive"))
    )
    (net (code "90") (name "Net-(U$90-P)") (class "Default")
      (node (ref "J5") (pin "P$10") (pinfunction "P$10_P$10") (pintype "bidirectional"))
      (node (ref "U$90") (pin "1") (pinfunction "P_1") (pintype "passive"))
    )
    (net (code "91") (name "Net-(U$91-P)") (class "Default")
      (node (ref "J5") (pin "P$11") (pinfunction "P$11_P$11") (pintype "bidirectional"))
      (node (ref "U$91") (pin "1") (pinfunction "P_1") (pintype "passive"))
    )
    (net (code "92") (name "Net-(U$92-P)") (class "Default")
      (node (ref "J5") (pin "P$12") (pinfunction "P$12_P$12") (pintype "bidirectional"))
      (node (ref "U$92") (pin "1") (pinfunction "P_1") (pintype "passive"))
    )
    (net (code "93") (name "Net-(U$93-P)") (class "Default")
      (node (ref "J5") (pin "P$13") (pinfunction "P$13_P$13") (pintype "bidirectional"))
      (node (ref "U$93") (pin "1") (pinfunction "P_1") (pintype "passive"))
    )
    (net (code "94") (name "Net-(U$94-P)") (class "Default")
      (node (ref "J5") (pin "P$14") (pinfunction "P$14_P$14") (pintype "bidirectional"))
      (node (ref "U$94") (pin "1") (pinfunction "P_1") (pintype "passive"))
    )
    (net (code "95") (name "Net-(U$95-P)") (class "Default")
      (node (ref "J5") (pin "P$15") (pinfunction "P$15_P$15") (pintype "bidirectional"))
      (node (ref "U$95") (pin "1") (pinfunction "P_1") (pintype "passive"))
    )
    (net (code "96") (name "Net-(U$96-P)") (class "Default")
      (node (ref "J5") (pin "P$16") (pinfunction "P$16_P$16") (pintype "bidirectional"))
      (node (ref "U$96") (pin "1") (pinfunction "P_1") (pintype "passive"))
    )
    (net (code "97") (name "Net-(U$97-P)") (class "Default")
      (node (ref "J5") (pin "P$17") (pinfunction "P$17_P$17") (pintype "bidirectional"))
      (node (ref "U$97") (pin "1") (pinfunction "P_1") (pintype "passive"))
    )
    (net (code "98") (name "Net-(U$98-P)") (class "Default")
      (node (ref "J5") (pin "P$18") (pinfunction "P$18_P$18") (pintype "bidirectional"))
      (node (ref "U$98") (pin "1") (pinfunction "P_1") (pintype "passive"))
    )
    (net (code "99") (name "Net-(U$99-P)") (class "Default")
      (node (ref "J5") (pin "P$19") (pinfunction "P$19_P$19") (pintype "bidirectional"))
      (node (ref "U$99") (pin "1") (pinfunction "P_1") (pintype "passive"))
    )
    (net (code "100") (name "Net-(U$100-P)") (class "Default")
      (node (ref "J5") (pin "P$20") (pinfunction "P$20_P$20") (pintype "bidirectional"))
      (node (ref "U$100") (pin "1") (pinfunction "P_1") (pintype "passive"))
    )
    (net (code "101") (name "Net-(U$101-P)") (class "Default")
      (node (ref "J5") (pin "P$21") (pinfunction "P$21_P$21") (pintype "bidirectional"))
      (node (ref "U$101") (pin "1") (pinfunction "P_1") (pintype "passive"))
    )
    (net (code "102") (name "Net-(U$102-P)") (class "Default")
      (node (ref "J5") (pin "P$22") (pinfunction "P$22_P$22") (pintype "bidirectional"))
      (node (ref "U$102") (pin "1") (pinfunction "P_1") (pintype "passive"))
    )
    (net (code "103") (name "Net-(U$103-P)") (class "Default")
      (node (ref "J5") (pin "P$23") (pinfunction "P$23_P$23") (pintype "bidirectional"))
      (node (ref "U$103") (pin "1") (pinfunction "P_1") (pintype "passive"))
    )
    (net (code "104") (name "Net-(U$104-P)") (class "Default")
      (node (ref "J5") (pin "P$24") (pinfunction "P$24_P$24") (pintype "bidirectional"))
      (node (ref "U$104") (pin "1") (pinfunction "P_1") (pintype "passive"))
    )
    (net (code "105") (name "Net-(U$105-P)") (class "Default")
      (node (ref "J6") (pin "P$1") (pinfunction "P$1_P$1") (pintype "bidirectional"))
      (node (ref "U$105") (pin "1") (pinfunction "P_1") (pintype "passive"))
    )
    (net (code "106") (name "Net-(U$106-P)") (class "Default")
      (node (ref "J6") (pin "P$2") (pinfunction "P$2_P$2") (pintype "bidirectional"))
      (node (ref "U$106") (pin "1") (pinfunction "P_1") (pintype "passive"))
    )
    (net (code "107") (name "Net-(U$107-P)") (class "Default")
      (node (ref "J6") (pin "P$3") (pinfunction "P$3_P$3") (pintype "bidirectional"))
      (node (ref "U$107") (pin "1") (pinfunction "P_1") (pintype "passive"))
    )
    (net (code "108") (name "Net-(U$108-P)") (class "Default")
      (node (ref "J6") (pin "P$4") (pinfunction "P$4_P$4") (pintype "bidirectional"))
      (node (ref "U$108") (pin "1") (pinfunction "P_1") (pintype "passive"))
    )
    (net (code "109") (name "Net-(U$109-P)") (class "Default")
      (node (ref "J6") (pin "P$5") (pinfunction "P$5_P$5") (pintype "bidirectional"))
      (node (ref "U$109") (pin "1") (pinfunction "P_1") (pintype "passive"))
    )
    (net (code "110") (name "Net-(U$110-P)") (class "Default")
      (node (ref "J6") (pin "P$6") (pinfunction "P$6_P$6") (pintype "bidirectional"))
      (node (ref "U$110") (pin "1") (pinfunction "P_1") (pintype "passive"))
    )
    (net (code "111") (name "Net-(U$111-P)") (class "Default")
      (node (ref "J6") (pin "P$7") (pinfunction "P$7_P$7") (pintype "bidirectional"))
      (node (ref "U$111") (pin "1") (pinfunction "P_1") (pintype "passive"))
    )
    (net (code "112") (name "Net-(U$112-P)") (class "Default")
      (node (ref "J6") (pin "P$8") (pinfunction "P$8_P$8") (pintype "bidirectional"))
      (node (ref "U$112") (pin "1") (pinfunction "P_1") (pintype "passive"))
    )
    (net (code "113") (name "Net-(U$113-P)") (class "Default")
      (node (ref "J6") (pin "P$9") (pinfunction "P$9_P$9") (pintype "bidirectional"))
      (node (ref "U$113") (pin "1") (pinfunction "P_1") (pintype "passive"))
    )
    (net (code "114") (name "Net-(U$114-P)") (class "Default")
      (node (ref "J6") (pin "P$10") (pinfunction "P$10_P$10") (pintype "bidirectional"))
      (node (ref "U$114") (pin "1") (pinfunction "P_1") (pintype "passive"))
    )
    (net (code "115") (name "Net-(U$115-P)") (class "Default")
      (node (ref "J6") (pin "P$11") (pinfunction "P$11_P$11") (pintype "bidirectional"))
      (node (ref "U$115") (pin "1") (pinfunction "P_1") (pintype "passive"))
    )
    (net (code "116") (name "Net-(U$116-P)") (class "Default")
      (node (ref "J6") (pin "P$12") (pinfunction "P$12_P$12") (pintype "bidirectional"))
      (node (ref "U$116") (pin "1") (pinfunction "P_1") (pintype "passive"))
    )
    (net (code "117") (name "Net-(U$117-P)") (class "Default")
      (node (ref "J6") (pin "P$13") (pinfunction "P$13_P$13") (pintype "bidirectional"))
      (node (ref "U$117") (pin "1") (pinfunction "P_1") (pintype "passive"))
    )
    (net (code "118") (name "Net-(U$118-P)") (class "Default")
      (node (ref "J6") (pin "P$14") (pinfunction "P$14_P$14") (pintype "bidirectional"))
      (node (ref "U$118") (pin "1") (pinfunction "P_1") (pintype "passive"))
    )
    (net (code "119") (name "Net-(U$119-P)") (class "Default")
      (node (ref "J6") (pin "P$15") (pinfunction "P$15_P$15") (pintype "bidirectional"))
      (node (ref "U$119") (pin "1") (pinfunction "P_1") (pintype "passive"))
    )
    (net (code "120") (name "Net-(U$120-P)") (class "Default")
      (node (ref "J6") (pin "P$16") (pinfunction "P$16_P$16") (pintype "bidirectional"))
      (node (ref "U$120") (pin "1") (pinfunction "P_1") (pintype "passive"))
    )
    (net (code "121") (name "Net-(U$121-P)") (class "Default")
      (node (ref "J6") (pin "P$17") (pinfunction "P$17_P$17") (pintype "bidirectional"))
      (node (ref "U$121") (pin "1") (pinfunction "P_1") (pintype "passive"))
    )
    (net (code "122") (name "Net-(U$122-P)") (class "Default")
      (node (ref "J6") (pin "P$18") (pinfunction "P$18_P$18") (pintype "bidirectional"))
      (node (ref "U$122") (pin "1") (pinfunction "P_1") (pintype "passive"))
    )
    (net (code "123") (name "Net-(U$123-P)") (class "Default")
      (node (ref "J6") (pin "P$19") (pinfunction "P$19_P$19") (pintype "bidirectional"))
      (node (ref "U$123") (pin "1") (pinfunction "P_1") (pintype "passive"))
    )
    (net (code "124") (name "Net-(U$124-P)") (class "Default")
      (node (ref "J6") (pin "P$20") (pinfunction "P$20_P$20") (pintype "bidirectional"))
      (node (ref "U$124") (pin "1") (pinfunction "P_1") (pintype "passive"))
    )
    (net (code "125") (name "Net-(U$125-P)") (class "Default")
      (node (ref "J6") (pin "P$21") (pinfunction "P$21_P$21") (pintype "bidirectional"))
      (node (ref "U$125") (pin "1") (pinfunction "P_1") (pintype "passive"))
    )
    (net (code "126") (name "Net-(U$126-P)") (class "Default")
      (node (ref "J6") (pin "P$22") (pinfunction "P$22_P$22") (pintype "bidirectional"))
      (node (ref "U$126") (pin "1") (pinfunction "P_1") (pintype "passive"))
    )
    (net (code "127") (name "Net-(U$127-P)") (class "Default")
      (node (ref "J6") (pin "P$23") (pinfunction "P$23_P$23") (pintype "bidirectional"))
      (node (ref "U$127") (pin "1") (pinfunction "P_1") (pintype "passive"))
    )
    (net (code "128") (name "Net-(U$128-P)") (class "Default")
      (node (ref "J6") (pin "P$24") (pinfunction "P$24_P$24") (pintype "bidirectional"))
      (node (ref "U$128") (pin "1") (pinfunction "P_1") (pintype "passive"))
    )
  )
)
